# MCU_1.net
KiCad netlist of a schematic drawn in Altium Designer
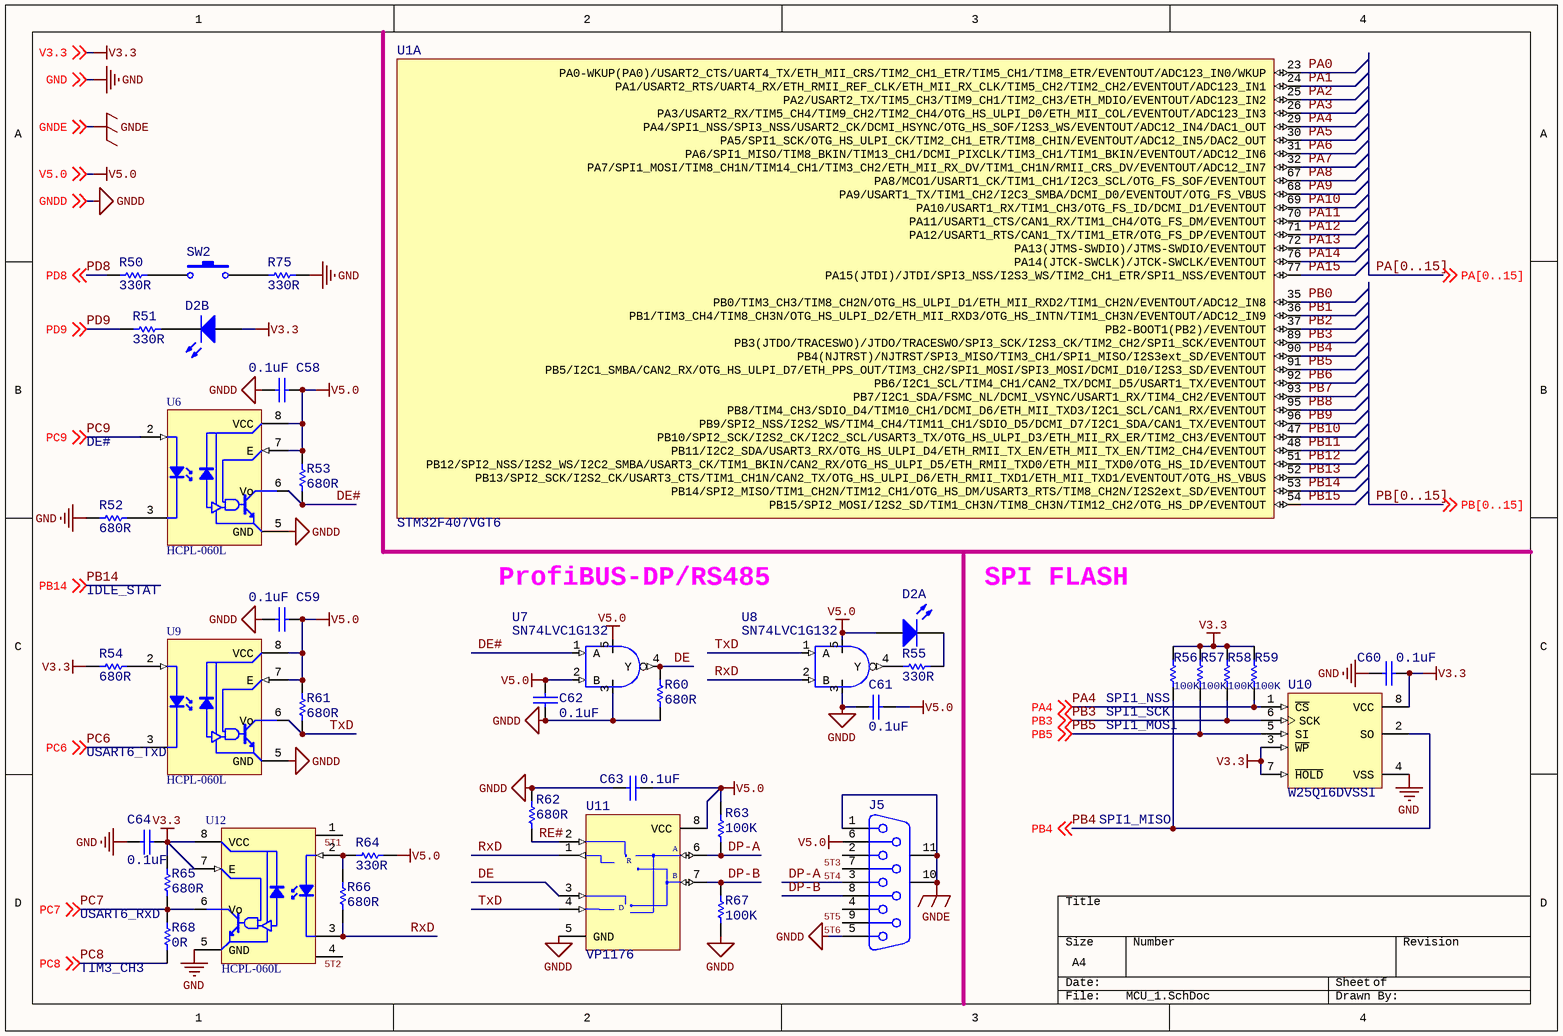
[diagram p0: MCU_1.SchDoc]

(export (version "E")
  (design (tool "Eeschema 10.0.6"))
  (components
    (comp (ref "C58")
      (value "0.1uF")
      (footprint "C1608(0603)")
      (description "Capacitor")
      (libsource (lib "input") (part "CAP"))
    )
    (comp (ref "C59")
      (value "0.1uF")
      (footprint "C1608(0603)")
      (description "Capacitor")
      (libsource (lib "input") (part "CAP"))
    )
    (comp (ref "C60")
      (value "0.1uF")
      (footprint "C1608(0603)")
      (description "Capacitor")
      (libsource (lib "input") (part "CAP"))
    )
    (comp (ref "C61")
      (value "0.1uF")
      (footprint "C1608(0603)")
      (description "Capacitor")
      (libsource (lib "input") (part "CAP"))
    )
    (comp (ref "C62")
      (value "0.1uF")
      (footprint "C1608(0603)")
      (description "Capacitor")
      (libsource (lib "input") (part "CAP"))
    )
    (comp (ref "C63")
      (value "0.1uF")
      (footprint "C1608(0603)")
      (description "Capacitor")
      (libsource (lib "input") (part "CAP"))
    )
    (comp (ref "C64")
      (value "0.1uF")
      (footprint "C1608(0603)")
      (description "Capacitor")
      (libsource (lib "input") (part "CAP"))
    )
    (comp (ref "D2")
      (value "LED-2")
      (footprint "LED-2")
      (description "Typical INFRARED GaAs LED")
      (fields (field (name "PUBLISHER") "Altium Limited"))
      (libsource (lib "SL-DPT100") (part "LED-2"))
    )
    (comp (ref "J5")
      (value "D Connector 9")
      (footprint "DB9F")
      (description "Receptacle Assembly, 9 Position, Right Angle")
      (fields (field (name "PUBLISHER") "Altium Limited"))
      (libsource (lib "Miscellaneous Connectors") (part "D Connector 9"))
    )
    (comp (ref "R50")
      (value "330R")
      (footprint "R1608(0603)")
      (description "Semiconductor Resistor")
      (fields (field (name "PUBLISHER") "Altium Limited"))
      (libsource (lib "Miscellaneous Devices") (part "Res Semi"))
    )
    (comp (ref "R51")
      (value "330R")
      (footprint "R1608(0603)")
      (description "Semiconductor Resistor")
      (fields (field (name "PUBLISHER") "Altium Limited"))
      (libsource (lib "Miscellaneous Devices") (part "Res Semi"))
    )
    (comp (ref "R52")
      (value "680R")
      (footprint "R1608(0603)")
      (description "Semiconductor Resistor")
      (fields (field (name "PUBLISHER") "Altium Limited"))
      (libsource (lib "Miscellaneous Devices") (part "Res Semi"))
    )
    (comp (ref "R53")
      (value "680R")
      (footprint "R1608(0603)")
      (description "Semiconductor Resistor")
      (fields (field (name "PUBLISHER") "Altium Limited"))
      (libsource (lib "Miscellaneous Devices") (part "Res Semi"))
    )
    (comp (ref "R54")
      (value "680R")
      (footprint "R1608(0603)")
      (description "Semiconductor Resistor")
      (fields (field (name "PUBLISHER") "Altium Limited"))
      (libsource (lib "Miscellaneous Devices") (part "Res Semi"))
    )
    (comp (ref "R55")
      (value "330R")
      (footprint "R1608(0603)")
      (description "Semiconductor Resistor")
      (fields (field (name "PUBLISHER") "Altium Limited"))
      (libsource (lib "Miscellaneous Devices") (part "Res Semi"))
    )
    (comp (ref "R56")
      (value "100K")
      (footprint "R1608(0603)")
      (description "Semiconductor Resistor")
      (fields (field (name "PUBLISHER") "Altium Limited"))
      (libsource (lib "Miscellaneous Devices") (part "Res Semi"))
    )
    (comp (ref "R57")
      (value "100K")
      (footprint "R1608(0603)")
      (description "Semiconductor Resistor")
      (fields (field (name "PUBLISHER") "Altium Limited"))
      (libsource (lib "Miscellaneous Devices") (part "Res Semi"))
    )
    (comp (ref "R58")
      (value "100K")
      (footprint "R1608(0603)")
      (description "Semiconductor Resistor")
      (fields (field (name "PUBLISHER") "Altium Limited"))
      (libsource (lib "Miscellaneous Devices") (part "Res Semi"))
    )
    (comp (ref "R59")
      (value "100K")
      (footprint "R1608(0603)")
      (description "Semiconductor Resistor")
      (fields (field (name "PUBLISHER") "Altium Limited"))
      (libsource (lib "Miscellaneous Devices") (part "Res Semi"))
    )
    (comp (ref "R60")
      (value "680R")
      (footprint "R1608(0603)")
      (description "Semiconductor Resistor")
      (fields (field (name "PUBLISHER") "Altium Limited"))
      (libsource (lib "Miscellaneous Devices") (part "Res Semi"))
    )
    (comp (ref "R61")
      (value "680R")
      (footprint "R1608(0603)")
      (description "Semiconductor Resistor")
      (fields (field (name "PUBLISHER") "Altium Limited"))
      (libsource (lib "Miscellaneous Devices") (part "Res Semi"))
    )
    (comp (ref "R62")
      (value "680R")
      (footprint "R1608(0603)")
      (description "Semiconductor Resistor")
      (fields (field (name "PUBLISHER") "Altium Limited"))
      (libsource (lib "Miscellaneous Devices") (part "Res Semi"))
    )
    (comp (ref "R63")
      (value "100K")
      (footprint "R1608(0603)")
      (description "Semiconductor Resistor")
      (fields (field (name "PUBLISHER") "Altium Limited"))
      (libsource (lib "Miscellaneous Devices") (part "Res Semi"))
    )
    (comp (ref "R64")
      (value "330R")
      (footprint "R1608(0603)")
      (description "Semiconductor Resistor")
      (fields (field (name "PUBLISHER") "Altium Limited"))
      (libsource (lib "Miscellaneous Devices") (part "Res Semi"))
    )
    (comp (ref "R65")
      (value "680R")
      (footprint "R1608(0603)")
      (description "Semiconductor Resistor")
      (fields (field (name "PUBLISHER") "Altium Limited"))
      (libsource (lib "Miscellaneous Devices") (part "Res Semi"))
    )
    (comp (ref "R66")
      (value "680R")
      (footprint "R1608(0603)")
      (description "Semiconductor Resistor")
      (fields (field (name "PUBLISHER") "Altium Limited"))
      (libsource (lib "Miscellaneous Devices") (part "Res Semi"))
    )
    (comp (ref "R67")
      (value "100K")
      (footprint "R1608(0603)")
      (description "Semiconductor Resistor")
      (fields (field (name "PUBLISHER") "Altium Limited"))
      (libsource (lib "Miscellaneous Devices") (part "Res Semi"))
    )
    (comp (ref "R68")
      (value "0R")
      (footprint "R1608(0603)")
      (description "Semiconductor Resistor")
      (fields (field (name "PUBLISHER") "Altium Limited"))
      (libsource (lib "Miscellaneous Devices") (part "Res Semi"))
    )
    (comp (ref "R75")
      (value "330R")
      (footprint "R1608(0603)")
      (description "Semiconductor Resistor")
      (fields (field (name "PUBLISHER") "Altium Limited"))
      (libsource (lib "Miscellaneous Devices") (part "Res Semi"))
    )
    (comp (ref "SW2")
      (value "SW-PB")
      (footprint "KEY 4.5x4.5x4.3mm")
      (description "Switch")
      (fields (field (name "PUBLISHER") "Altium Limited"))
      (libsource (lib "Miscellaneous Devices") (part "SW-PB"))
    )
    (comp (ref "U1")
      (value "STM32F407VGT6")
      (footprint "TQFP100_N")
      (libsource (lib "STMicroelectronics STM32 F4") (part "STM32F407VGT6"))
    )
    (comp (ref "U6") (value "HCPL-060L") (footprint "SO8_M") (libsource (lib "SL-DPT100") (part "HCPL-060")))
    (comp (ref "U7")
      (value "SN74LVC1G132")
      (footprint "SOT23-5_N")
      (libsource (lib "SL-DPT100") (part "SN74LVC1G132"))
    )
    (comp (ref "U8")
      (value "SN74LVC1G132")
      (footprint "SOT23-5_N")
      (libsource (lib "SL-DPT100") (part "SN74LVC1G132"))
    )
    (comp (ref "U9") (value "HCPL-060L") (footprint "SO8_M") (libsource (lib "SL-DPT100") (part "HCPL-060")))
    (comp (ref "U10")
      (value "W25Q16DVSSI")
      (footprint "SOIC8_M")
      (description "64K SPI Bus Serial EEPROM, 8-Pin SOIC, Industrial Temperature")
      (fields (field (name "PUBLISHER") "Altium Limited"))
      (libsource (lib "*") (part "25AA640A-I/SN"))
    )
    (comp (ref "U11")
      (value "VP1176")
      (footprint "SO8_M")
      (description "Low-Power, Slew-Rate-Limited RS-485/RS-422 Transceiver")
      (fields (field (name "PUBLISHER") "Altium Limited"))
      (libsource (lib "Maxim Communication Transceiver") (part "MAX485ESA"))
    )
    (comp (ref "U12") (value "HCPL-060L") (footprint "SO8_M") (libsource (lib "") (part "HCPL-060_1")))
  )
  (nets
    (net (code "1") (name "/5T1") (class "Default")
      (node (ref "U12") (pin "1") (pinfunction "1_1") (pintype "passive"))
    )
    (net (code "2") (name "/5T2") (class "Default")
      (node (ref "U12") (pin "4") (pinfunction "4_4") (pintype "passive"))
    )
    (net (code "3") (name "/5T3") (class "Default")
      (node (ref "J5") (pin "2") (pinfunction "2_2") (pintype "passive"))
    )
    (net (code "4") (name "/5T4") (class "Default")
      (node (ref "J5") (pin "7") (pinfunction "7_7") (pintype "passive"))
    )
    (net (code "5") (name "/5T5") (class "Default")
      (node (ref "J5") (pin "4") (pinfunction "4_4") (pintype "passive"))
    )
    (net (code "6") (name "/5T6") (class "Default")
      (node (ref "J5") (pin "9") (pinfunction "9_9") (pintype "passive"))
    )
    (net (code "7") (name "/DE") (class "Default")
      (node (ref "R60") (pin "2") (pinfunction "2_2") (pintype "passive"))
      (node (ref "U11") (pin "3") (pinfunction "DE_3") (pintype "input"))
      (node (ref "U7") (pin "4") (pinfunction "Y_4") (pintype "output"))
    )
    (net (code "8") (name "/DE#") (class "Default")
      (node (ref "R53") (pin "1") (pinfunction "1_1") (pintype "passive"))
      (node (ref "U6") (pin "6") (pinfunction "Vo_6") (pintype "open_collector"))
      (node (ref "U7") (pin "1") (pinfunction "A_1") (pintype "input"))
    )
    (net (code "9") (name "/DP-A") (class "Default")
      (node (ref "J5") (pin "3") (pinfunction "3_3") (pintype "passive"))
      (node (ref "R63") (pin "1") (pinfunction "1_1") (pintype "passive"))
      (node (ref "U11") (pin "6") (pinfunction "A_6") (pintype "bidirectional"))
    )
    (net (code "10") (name "/DP-B") (class "Default")
      (node (ref "J5") (pin "8") (pinfunction "8_8") (pintype "passive"))
      (node (ref "R67") (pin "2") (pinfunction "2_2") (pintype "passive"))
      (node (ref "U11") (pin "7") (pinfunction "B_7") (pintype "bidirectional"))
    )
    (net (code "11") (name "/RE#") (class "Default")
      (node (ref "R62") (pin "1") (pinfunction "1_1") (pintype "passive"))
      (node (ref "U11") (pin "2") (pinfunction "~{RE}_2") (pintype "input"))
    )
    (net (code "12") (name "/RxD") (class "Default")
      (node (ref "R66") (pin "1") (pinfunction "1_1") (pintype "passive"))
      (node (ref "U11") (pin "1") (pinfunction "RO_1") (pintype "output"))
      (node (ref "U12") (pin "3") (pinfunction "-_3") (pintype "passive"))
      (node (ref "U8") (pin "2") (pinfunction "B_2") (pintype "input"))
    )
    (net (code "13") (name "/TxD") (class "Default")
      (node (ref "R61") (pin "1") (pinfunction "1_1") (pintype "passive"))
      (node (ref "U11") (pin "4") (pinfunction "DI_4") (pintype "input"))
      (node (ref "U8") (pin "1") (pinfunction "A_1") (pintype "input"))
      (node (ref "U9") (pin "6") (pinfunction "Vo_6") (pintype "open_collector"))
    )
    (net (code "14") (name "GND") (class "Default")
      (node (ref "C60") (pin "2") (pinfunction "2_2") (pintype "passive"))
      (node (ref "C64") (pin "2") (pinfunction "2_2") (pintype "passive"))
      (node (ref "R52") (pin "1") (pinfunction "1_1") (pintype "passive"))
      (node (ref "R75") (pin "2") (pinfunction "2_2") (pintype "passive"))
      (node (ref "U10") (pin "4") (pinfunction "VSS_4") (pintype "power_in"))
      (node (ref "U12") (pin "5") (pinfunction "GND_5") (pintype "power_in"))
    )
    (net (code "15") (name "GNDD") (class "Default")
      (node (ref "C58") (pin "2") (pinfunction "2_2") (pintype "passive"))
      (node (ref "C59") (pin "2") (pinfunction "2_2") (pintype "passive"))
      (node (ref "C61") (pin "1") (pinfunction "1_1") (pintype "passive"))
      (node (ref "C62") (pin "2") (pinfunction "2_2") (pintype "passive"))
      (node (ref "C63") (pin "2") (pinfunction "2_2") (pintype "passive"))
      (node (ref "J5") (pin "5") (pinfunction "5_5") (pintype "passive"))
      (node (ref "R60") (pin "1") (pinfunction "1_1") (pintype "passive"))
      (node (ref "R62") (pin "2") (pinfunction "2_2") (pintype "passive"))
      (node (ref "R67") (pin "1") (pinfunction "1_1") (pintype "passive"))
      (node (ref "U11") (pin "5") (pinfunction "GND_5") (pintype "power_in"))
      (node (ref "U6") (pin "5") (pinfunction "GND_5") (pintype "power_in"))
      (node (ref "U7") (pin "3") (pinfunction "GND_3") (pintype "power_in"))
      (node (ref "U8") (pin "3") (pinfunction "GND_3") (pintype "power_in"))
      (node (ref "U9") (pin "5") (pinfunction "GND_5") (pintype "power_in"))
    )
    (net (code "16") (name "GNDE") (class "Default")
      (node (ref "J5") (pin "1") (pinfunction "1_1") (pintype "passive"))
      (node (ref "J5") (pin "10") (pinfunction "MH1_10") (pintype "passive"))
      (node (ref "J5") (pin "11") (pinfunction "MH2_11") (pintype "passive"))
    )
    (net (code "17") (name "Net-(D2A-K1)") (class "Default")
      (node (ref "D2") (pin "2") (pinfunction "K1_2") (pintype "passive"))
      (node (ref "R55") (pin "2") (pinfunction "2_2") (pintype "passive"))
    )
    (net (code "18") (name "Net-(D2B-K2)") (class "Default")
      (node (ref "D2") (pin "4") (pinfunction "K2_4") (pintype "passive"))
      (node (ref "R51") (pin "2") (pinfunction "2_2") (pintype "passive"))
    )
    (net (code "19") (name "Net-(R50-Pad2)") (class "Default")
      (node (ref "R50") (pin "2") (pinfunction "2_2") (pintype "passive"))
      (node (ref "SW2") (pin "1") (pinfunction "1_1") (pintype "passive"))
    )
    (net (code "20") (name "Net-(R75-Pad1)") (class "Default")
      (node (ref "R75") (pin "1") (pinfunction "1_1") (pintype "passive"))
      (node (ref "SW2") (pin "2") (pinfunction "2_2") (pintype "passive"))
    )
    (net (code "21") (name "Net-(U6--)") (class "Default")
      (node (ref "R52") (pin "2") (pinfunction "2_2") (pintype "passive"))
      (node (ref "U6") (pin "3") (pinfunction "-_3") (pintype "passive"))
    )
    (net (code "22") (name "Net-(U8-Y)") (class "Default")
      (node (ref "R55") (pin "1") (pinfunction "1_1") (pintype "passive"))
      (node (ref "U8") (pin "4") (pinfunction "Y_4") (pintype "output"))
    )
    (net (code "23") (name "Net-(U9-+)") (class "Default")
      (node (ref "R54") (pin "2") (pinfunction "2_2") (pintype "passive"))
      (node (ref "U9") (pin "2") (pinfunction "+_2") (pintype "input"))
    )
    (net (code "24") (name "Net-(U12-+)") (class "Default")
      (node (ref "R64") (pin "1") (pinfunction "1_1") (pintype "passive"))
      (node (ref "R66") (pin "2") (pinfunction "2_2") (pintype "passive"))
      (node (ref "U12") (pin "2") (pinfunction "+_2") (pintype "input"))
    )
    (net (code "25") (name "PA0") (class "Default")
      (node (ref "U1") (pin "23") (pinfunction "PA0-WKUP(PA0)/USART2_CTS/UART4_TX/ETH_MII_CRS/TIM2_CH1_ETR/TIM5_CH1/TIM8_ETR/EVENTOUT/ADC123_IN0/WKUP_23") (pintype "bidirectional"))
    )
    (net (code "26") (name "PA1") (class "Default")
      (node (ref "U1") (pin "24") (pinfunction "PA1/USART2_RTS/UART4_RX/ETH_RMII_REF_CLK/ETH_MII_RX_CLK/TIM5_CH2/TIM2_CH2/EVENTOUT/ADC123_IN1_24") (pintype "bidirectional"))
    )
    (net (code "27") (name "PA2") (class "Default")
      (node (ref "U1") (pin "25") (pinfunction "PA2/USART2_TX/TIM5_CH3/TIM9_CH1/TIM2_CH3/ETH_MDIO/EVENTOUT/ADC123_IN2_25") (pintype "bidirectional"))
    )
    (net (code "28") (name "PA3") (class "Default")
      (node (ref "U1") (pin "26") (pinfunction "PA3/USART2_RX/TIM5_CH4/TIM9_CH2/TIM2_CH4/OTG_HS_ULPI_D0/ETH_MII_COL/EVENTOUT/ADC123_IN3_26") (pintype "bidirectional"))
    )
    (net (code "29") (name "PA4") (class "Default")
      (node (ref "R59") (pin "1") (pinfunction "1_1") (pintype "passive"))
      (node (ref "U1") (pin "29") (pinfunction "PA4/SPI1_NSS/SPI3_NSS/USART2_CK/DCMI_HSYNC/OTG_HS_SOF/I2S3_WS/EVENTOUT/ADC12_IN4/DAC1_OUT_29") (pintype "bidirectional"))
      (node (ref "U10") (pin "1") (pinfunction "~{CS}_1") (pintype "input"))
    )
    (net (code "30") (name "PA5") (class "Default")
      (node (ref "U1") (pin "30") (pinfunction "PA5/SPI1_SCK/OTG_HS_ULPI_CK/TIM2_CH1_ETR/TIM8_CHIN/EVENTOUT/ADC12_IN5/DAC2_OUT_30") (pintype "bidirectional"))
    )
    (net (code "31") (name "PA6") (class "Default")
      (node (ref "U1") (pin "31") (pinfunction "PA6/SPI1_MISO/TIM8_BKIN/TIM13_CH1/DCMI_PIXCLK/TIM3_CH1/TIM1_BKIN/EVENTOUT/ADC12_IN6_31") (pintype "bidirectional"))
    )
    (net (code "32") (name "PA7") (class "Default")
      (node (ref "U1") (pin "32") (pinfunction "PA7/SPI1_MOSI/TIM8_CH1N/TIM14_CH1/TIM3_CH2/ETH_MII_RX_DV/TIM1_CH1N/RMII_CRS_DV/EVENTOUT/ADC12_IN7_32") (pintype "bidirectional"))
    )
    (net (code "33") (name "PA8") (class "Default")
      (node (ref "U1") (pin "67") (pinfunction "PA8/MCO1/USART1_CK/TIM1_CH1/I2C3_SCL/OTG_FS_SOF/EVENTOUT_67") (pintype "bidirectional"))
    )
    (net (code "34") (name "PA9") (class "Default")
      (node (ref "U1") (pin "68") (pinfunction "PA9/USART1_TX/TIM1_CH2/I2C3_SMBA/DCMI_D0/EVENTOUT/OTG_FS_VBUS_68") (pintype "bidirectional"))
    )
    (net (code "35") (name "PA10") (class "Default")
      (node (ref "U1") (pin "69") (pinfunction "PA10/USART1_RX/TIM1_CH3/OTG_FS_ID/DCMI_D1/EVENTOUT_69") (pintype "bidirectional"))
    )
    (net (code "36") (name "PA11") (class "Default")
      (node (ref "U1") (pin "70") (pinfunction "PA11/USART1_CTS/CAN1_RX/TIM1_CH4/OTG_FS_DM/EVENTOUT_70") (pintype "bidirectional"))
    )
    (net (code "37") (name "PA12") (class "Default")
      (node (ref "U1") (pin "71") (pinfunction "PA12/USART1_RTS/CAN1_TX/TIM1_ETR/OTG_FS_DP/EVENTOUT_71") (pintype "bidirectional"))
    )
    (net (code "38") (name "PA13") (class "Default")
      (node (ref "U1") (pin "72") (pinfunction "PA13(JTMS-SWDIO)/JTMS-SWDIO/EVENTOUT_72") (pintype "bidirectional"))
    )
    (net (code "39") (name "PA14") (class "Default")
      (node (ref "U1") (pin "76") (pinfunction "PA14(JTCK-SWCLK)/JTCK-SWCLK/EVENTOUT_76") (pintype "bidirectional"))
    )
    (net (code "40") (name "PA15") (class "Default")
      (node (ref "U1") (pin "77") (pinfunction "PA15(JTDI)/JTDI/SPI3_NSS/I2S3_WS/TIM2_CH1_ETR/SPI1_NSS/EVENTOUT_77") (pintype "bidirectional"))
    )
    (net (code "42") (name "PB0") (class "Default")
      (node (ref "U1") (pin "35") (pinfunction "PB0/TIM3_CH3/TIM8_CH2N/OTG_HS_ULPI_D1/ETH_MII_RXD2/TIM1_CH2N/EVENTOUT/ADC12_IN8_35") (pintype "bidirectional"))
    )
    (net (code "43") (name "PB1") (class "Default")
      (node (ref "U1") (pin "36") (pinfunction "PB1/TIM3_CH4/TIM8_CH3N/OTG_HS_ULPI_D2/ETH_MII_RXD3/OTG_HS_INTN/TIM1_CH3N/EVENTOUT/ADC12_IN9_36") (pintype "bidirectional"))
    )
    (net (code "44") (name "PB2") (class "Default")
      (node (ref "U1") (pin "37") (pinfunction "PB2-BOOT1(PB2)/EVENTOUT_37") (pintype "bidirectional"))
    )
    (net (code "45") (name "PB3") (class "Default")
      (node (ref "R58") (pin "1") (pinfunction "1_1") (pintype "passive"))
      (node (ref "U1") (pin "89") (pinfunction "PB3(JTDO/TRACESWO)/JTDO/TRACESWO/SPI3_SCK/I2S3_CK/TIM2_CH2/SPI1_SCK/EVENTOUT_89") (pintype "bidirectional"))
      (node (ref "U10") (pin "6") (pinfunction "SCK_6") (pintype "input"))
    )
    (net (code "46") (name "PB4") (class "Default")
      (node (ref "R56") (pin "1") (pinfunction "1_1") (pintype "passive"))
      (node (ref "U1") (pin "90") (pinfunction "PB4(NJTRST)/NJTRST/SPI3_MISO/TIM3_CH1/SPI1_MISO/I2S3ext_SD/EVENTOUT_90") (pintype "bidirectional"))
      (node (ref "U10") (pin "2") (pinfunction "SO_2") (pintype "tri_state"))
    )
    (net (code "47") (name "PB5") (class "Default")
      (node (ref "R57") (pin "1") (pinfunction "1_1") (pintype "passive"))
      (node (ref "U1") (pin "91") (pinfunction "PB5/I2C1_SMBA/CAN2_RX/OTG_HS_ULPI_D7/ETH_PPS_OUT/TIM3_CH2/SPI1_MOSI/SPI3_MOSI/DCMI_D10/I2S3_SD/EVENTOUT_91") (pintype "bidirectional"))
      (node (ref "U10") (pin "5") (pinfunction "SI_5") (pintype "input"))
    )
    (net (code "48") (name "PB6") (class "Default")
      (node (ref "U1") (pin "92") (pinfunction "PB6/I2C1_SCL/TIM4_CH1/CAN2_TX/DCMI_D5/USART1_TX/EVENTOUT_92") (pintype "bidirectional"))
    )
    (net (code "49") (name "PB7") (class "Default")
      (node (ref "U1") (pin "93") (pinfunction "PB7/I2C1_SDA/FSMC_NL/DCMI_VSYNC/USART1_RX/TIM4_CH2/EVENTOUT_93") (pintype "bidirectional"))
    )
    (net (code "50") (name "PB8") (class "Default")
      (node (ref "U1") (pin "95") (pinfunction "PB8/TIM4_CH3/SDIO_D4/TIM10_CH1/DCMI_D6/ETH_MII_TXD3/I2C1_SCL/CAN1_RX/EVENTOUT_95") (pintype "bidirectional"))
    )
    (net (code "51") (name "PB9") (class "Default")
      (node (ref "U1") (pin "96") (pinfunction "PB9/SPI2_NSS/I2S2_WS/TIM4_CH4/TIM11_CH1/SDIO_D5/DCMI_D7/I2C1_SDA/CAN1_TX/EVENTOUT_96") (pintype "bidirectional"))
    )
    (net (code "52") (name "PB10") (class "Default")
      (node (ref "U1") (pin "47") (pinfunction "PB10/SPI2_SCK/I2S2_CK/I2C2_SCL/USART3_TX/OTG_HS_ULPI_D3/ETH_MII_RX_ER/TIM2_CH3/EVENTOUT_47") (pintype "bidirectional"))
    )
    (net (code "53") (name "PB11") (class "Default")
      (node (ref "U1") (pin "48") (pinfunction "PB11/I2C2_SDA/USART3_RX/OTG_HS_ULPI_D4/ETH_RMII_TX_EN/ETH_MII_TX_EN/TIM2_CH4/EVENTOUT_48") (pintype "bidirectional"))
    )
    (net (code "54") (name "PB12") (class "Default")
      (node (ref "U1") (pin "51") (pinfunction "PB12/SPI2_NSS/I2S2_WS/I2C2_SMBA/USART3_CK/TIM1_BKIN/CAN2_RX/OTG_HS_ULPI_D5/ETH_RMII_TXD0/ETH_MII_TXD0/OTG_HS_ID/EVENTOUT_51") (pintype "bidirectional"))
    )
    (net (code "55") (name "PB13") (class "Default")
      (node (ref "U1") (pin "52") (pinfunction "PB13/SPI2_SCK/I2S2_CK/USART3_CTS/TIM1_CH1N/CAN2_TX/OTG_HS_ULPI_D6/ETH_RMII_TXD1/ETH_MII_TXD1/EVENTOUT/OTG_HS_VBUS_52") (pintype "bidirectional"))
    )
    (net (code "56") (name "PB14") (class "Default")
      (node (ref "U1") (pin "53") (pinfunction "PB14/SPI2_MISO/TIM1_CH2N/TIM12_CH1/OTG_HS_DM/USART3_RTS/TIM8_CH2N/I2S2ext_SD/EVENTOUT_53") (pintype "bidirectional"))
    )
    (net (code "57") (name "PB15") (class "Default")
      (node (ref "U1") (pin "54") (pinfunction "PB15/SPI2_MOSI/I2S2_SD/TIM1_CH3N/TIM8_CH3N/TIM12_CH2/OTG_HS_DP/EVENTOUT_54") (pintype "bidirectional"))
    )
    (net (code "59") (name "PC6") (class "Default")
      (node (ref "U9") (pin "3") (pinfunction "-_3") (pintype "passive"))
    )
    (net (code "60") (name "PC7") (class "Default")
      (node (ref "R65") (pin "1") (pinfunction "1_1") (pintype "passive"))
      (node (ref "R68") (pin "2") (pinfunction "2_2") (pintype "passive"))
      (node (ref "U12") (pin "6") (pinfunction "Vo_6") (pintype "open_collector"))
    )
    (net (code "61") (name "PC8") (class "Default")
      (node (ref "R68") (pin "1") (pinfunction "1_1") (pintype "passive"))
    )
    (net (code "62") (name "PC9") (class "Default")
      (node (ref "U6") (pin "2") (pinfunction "+_2") (pintype "input"))
    )
    (net (code "63") (name "PD8") (class "Default")
      (node (ref "R50") (pin "1") (pinfunction "1_1") (pintype "passive"))
    )
    (net (code "64") (name "PD9") (class "Default")
      (node (ref "R51") (pin "1") (pinfunction "1_1") (pintype "passive"))
    )
    (net (code "65") (name "V3.3") (class "Default")
      (node (ref "C60") (pin "1") (pinfunction "1_1") (pintype "passive"))
      (node (ref "C64") (pin "1") (pinfunction "1_1") (pintype "passive"))
      (node (ref "D2") (pin "3") (pinfunction "A2_3") (pintype "passive"))
      (node (ref "R54") (pin "1") (pinfunction "1_1") (pintype "passive"))
      (node (ref "R56") (pin "2") (pinfunction "2_2") (pintype "passive"))
      (node (ref "R57") (pin "2") (pinfunction "2_2") (pintype "passive"))
      (node (ref "R58") (pin "2") (pinfunction "2_2") (pintype "passive"))
      (node (ref "R59") (pin "2") (pinfunction "2_2") (pintype "passive"))
      (node (ref "R65") (pin "2") (pinfunction "2_2") (pintype "passive"))
      (node (ref "U10") (pin "3") (pinfunction "~{WP}_3") (pintype "input"))
      (node (ref "U10") (pin "7") (pinfunction "~{HOLD}_7") (pintype "input"))
      (node (ref "U10") (pin "8") (pinfunction "VCC_8") (pintype "power_in"))
      (node (ref "U12") (pin "7") (pinfunction "E_7") (pintype "input"))
      (node (ref "U12") (pin "8") (pinfunction "VCC_8") (pintype "power_in"))
    )
    (net (code "66") (name "V5.0") (class "Default")
      (node (ref "C58") (pin "1") (pinfunction "1_1") (pintype "passive"))
      (node (ref "C59") (pin "1") (pinfunction "1_1") (pintype "passive"))
      (node (ref "C61") (pin "2") (pinfunction "2_2") (pintype "passive"))
      (node (ref "C62") (pin "1") (pinfunction "1_1") (pintype "passive"))
      (node (ref "C63") (pin "1") (pinfunction "1_1") (pintype "passive"))
      (node (ref "D2") (pin "1") (pinfunction "A1_1") (pintype "passive"))
      (node (ref "J5") (pin "6") (pinfunction "6_6") (pintype "passive"))
      (node (ref "R53") (pin "2") (pinfunction "2_2") (pintype "passive"))
      (node (ref "R61") (pin "2") (pinfunction "2_2") (pintype "passive"))
      (node (ref "R63") (pin "2") (pinfunction "2_2") (pintype "passive"))
      (node (ref "R64") (pin "2") (pinfunction "2_2") (pintype "passive"))
      (node (ref "U11") (pin "8") (pinfunction "VCC_8") (pintype "power_in"))
      (node (ref "U6") (pin "7") (pinfunction "E_7") (pintype "input"))
      (node (ref "U6") (pin "8") (pinfunction "VCC_8") (pintype "power_in"))
      (node (ref "U7") (pin "2") (pinfunction "B_2") (pintype "input"))
      (node (ref "U7") (pin "5") (pinfunction "VCC_5") (pintype "power_in"))
      (node (ref "U8") (pin "5") (pinfunction "VCC_5") (pintype "power_in"))
      (node (ref "U9") (pin "7") (pinfunction "E_7") (pintype "input"))
      (node (ref "U9") (pin "8") (pinfunction "VCC_8") (pintype "power_in"))
    )
    (net (code "67") (name "unconnected-(U6-Pad1)") (class "Default")
      (node (ref "U6") (pin "1") (pinfunction "1_1") (pintype "passive"))
    )
    (net (code "68") (name "unconnected-(U6-Pad4)") (class "Default")
      (node (ref "U6") (pin "4") (pinfunction "4_4") (pintype "passive"))
    )
    (net (code "69") (name "unconnected-(U9-Pad1)") (class "Default")
      (node (ref "U9") (pin "1") (pinfunction "1_1") (pintype "passive"))
    )
    (net (code "70") (name "unconnected-(U9-Pad4)") (class "Default")
      (node (ref "U9") (pin "4") (pinfunction "4_4") (pintype "passive"))
    )
  )
)
